# Solar_Water_Heater_Controller.net
KiCad netlist of a schematic drawn in Altium Designer
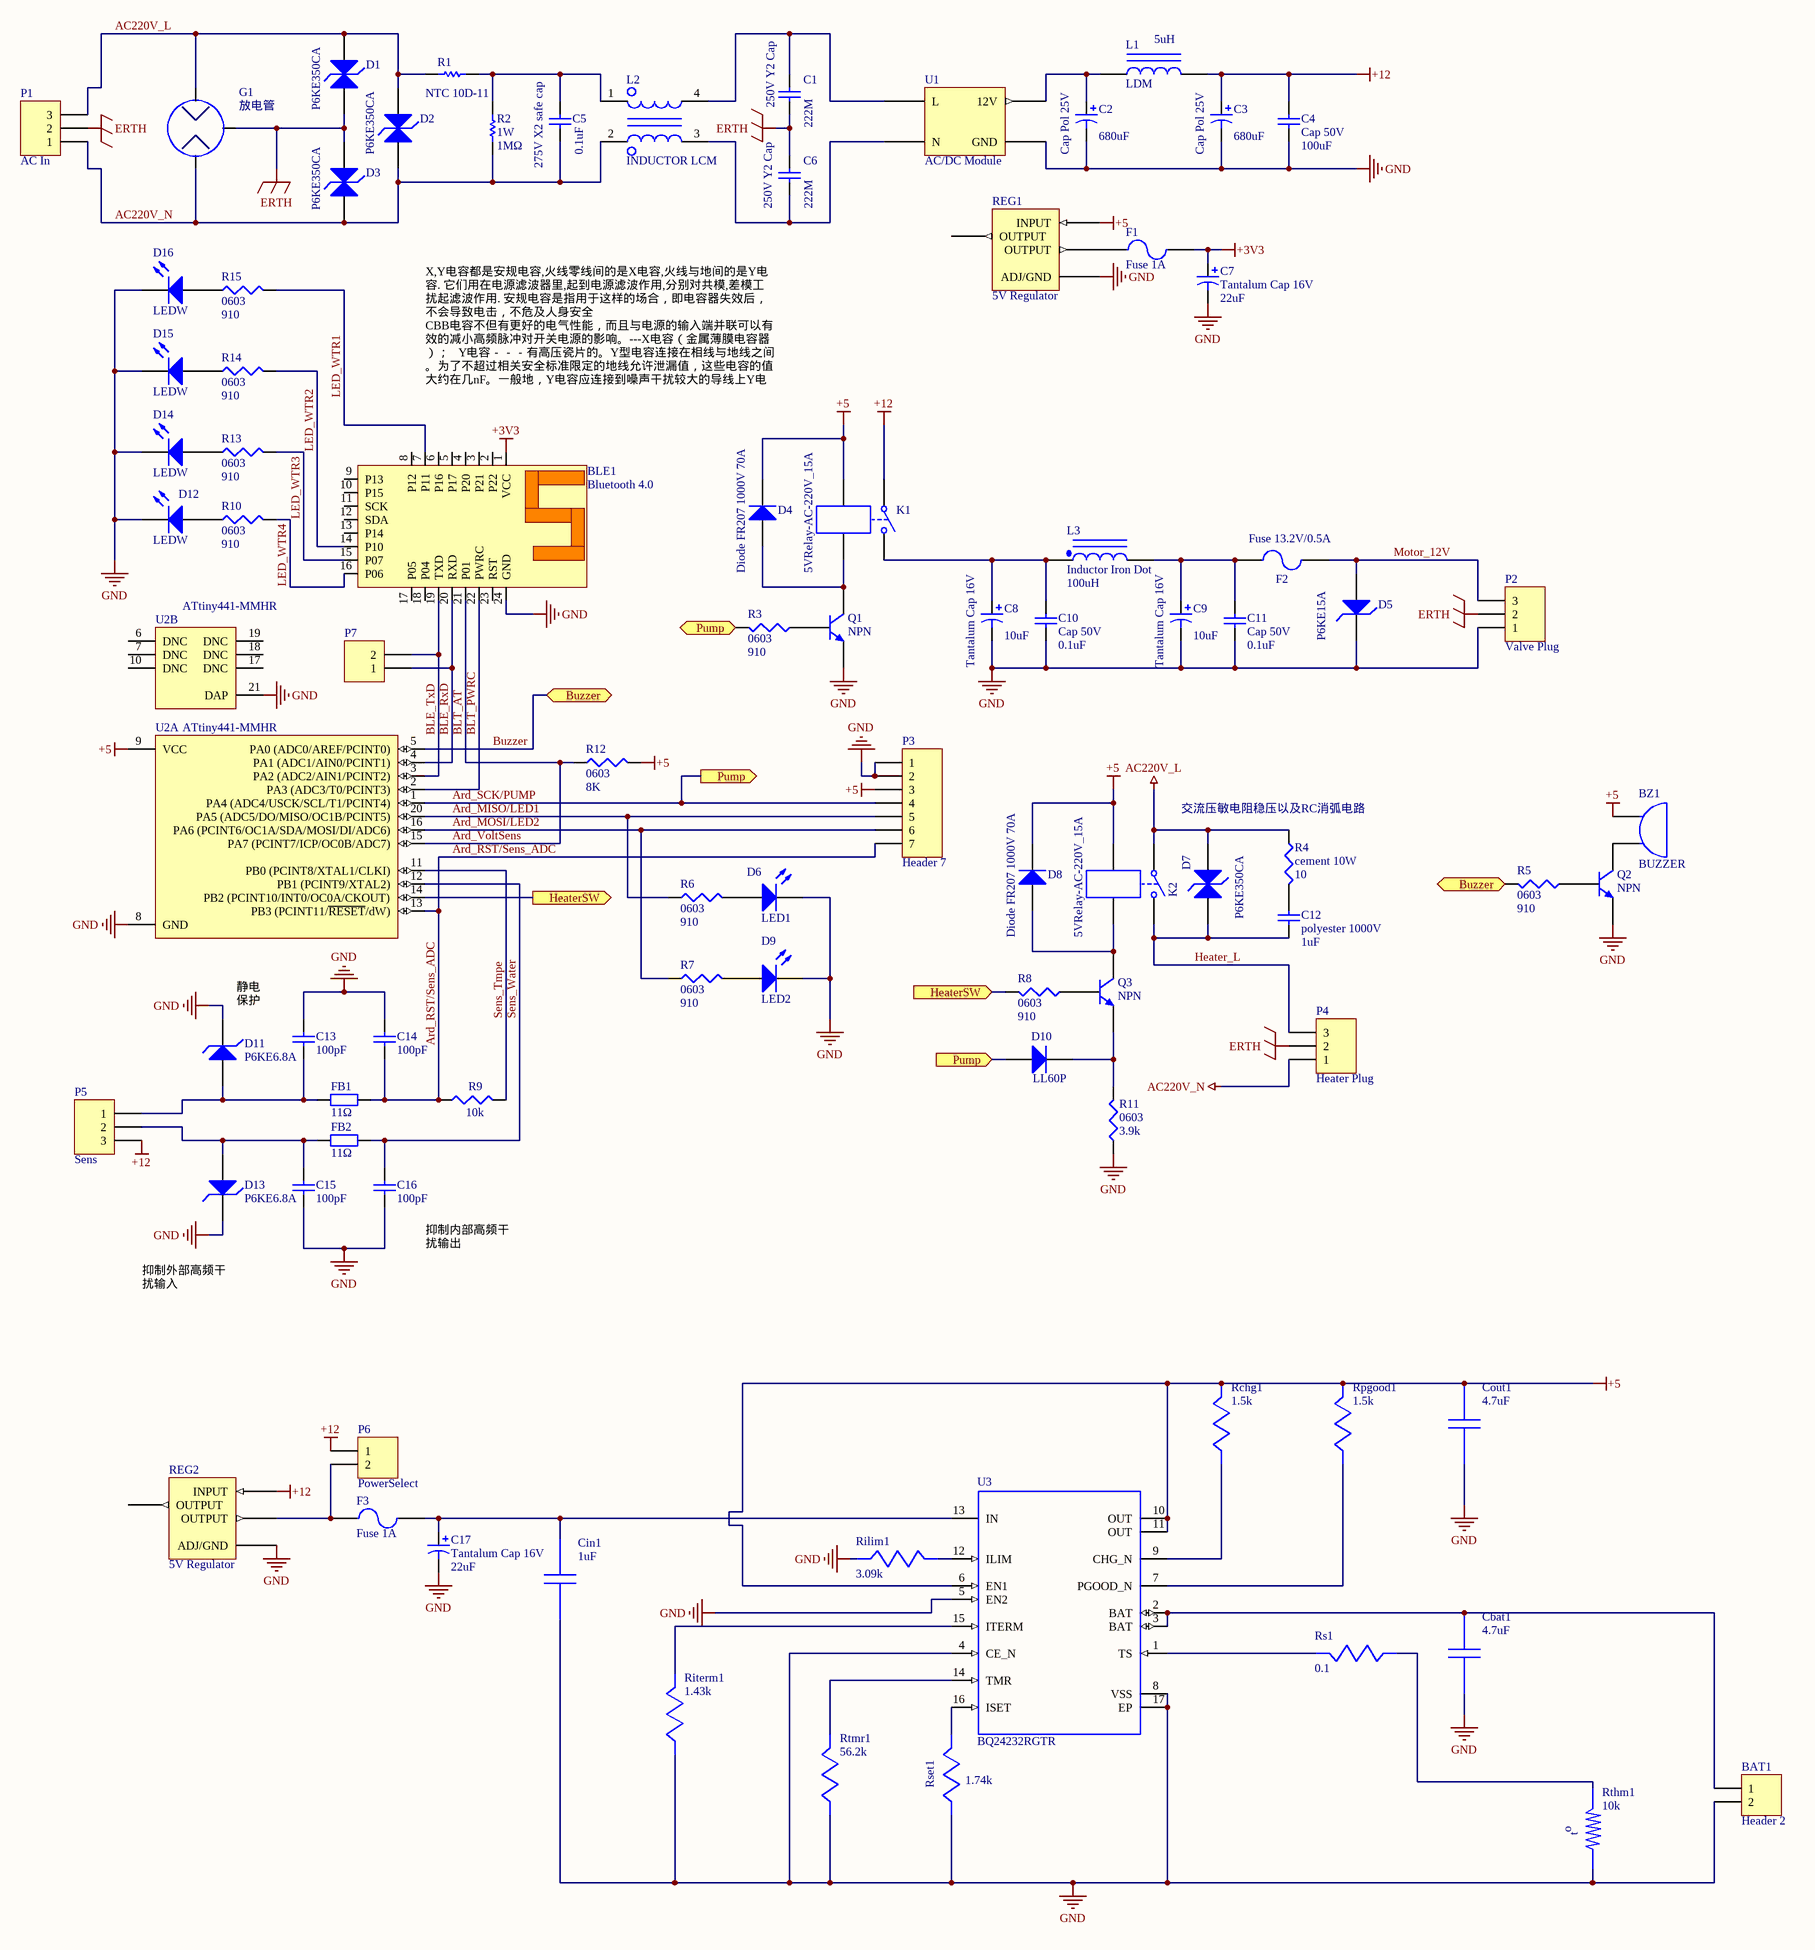
[diagram p0: Solar Water Heater Controller.SchDoc]

(export (version "E")
  (design (tool "Eeschema 10.0.6"))
  (components
    (comp (ref "BAT1")
      (value "Header 2")
      (footprint "HDR1X2")
      (description "Header, 2-Pin")
      (fields (field (name "PUBLISHER") "Altium Limited"))
      (libsource (lib "Miscellaneous Connectors") (part "Header 2"))
    )
    (comp (ref "BLE1")
      (value "Bluetooth 4.0")
      (footprint "JDY-08")
      (libsource (lib "JDY-08(原理图库)") (part "CC2541-Small"))
    )
    (comp (ref "BZ1")
      (value "BUZZER")
      (footprint "Buzzer")
      (description "5V有源蜂鸣器 电磁式 SOT塑封管 5V 12mm")
      (libsource (lib "杂元件库") (part "BUZZER"))
    )
    (comp (ref "C1")
      (value "250V Y2 Cap")
      (footprint "CapY2")
      (description "JNC222M 250V")
      (fields (field (name "ALTIUM_VALUE") "222M") (field (name "PUBLISHER") "Altium Limited"))
      (libsource (lib "Miscellaneous Devices") (part "Cap Semi"))
    )
    (comp (ref "C2")
      (value "Cap Pol 25V")
      (footprint "Cap680uf")
      (description "Polarized Capacitor (Radial)")
      (fields (field (name "ALTIUM_VALUE") "680uF") (field (name "PUBLISHER") "Altium Limited"))
      (libsource (lib "Miscellaneous Devices") (part "Cap Pol1"))
    )
    (comp (ref "C3")
      (value "Cap Pol 25V")
      (footprint "Cap680uf")
      (description "Polarized Capacitor (Radial)")
      (fields (field (name "ALTIUM_VALUE") "680uF") (field (name "PUBLISHER") "Altium Limited"))
      (libsource (lib "Miscellaneous Devices") (part "Cap Pol1"))
    )
    (comp (ref "C4")
      (value "Cap 50V")
      (footprint "1608[0603]")
      (description "Capacitor (Semiconductor SIM Model)")
      (fields (field (name "ALTIUM_VALUE") "100uF") (field (name "PUBLISHER") "Altium Limited"))
      (libsource (lib "Miscellaneous Devices") (part "Cap Semi"))
    )
    (comp (ref "C5")
      (value "275V X2 safe cap")
      (footprint "CapX2")
      (description "MPX104KV 275V X2安规电容")
      (fields (field (name "ALTIUM_VALUE") "0.1uF") (field (name "PUBLISHER") "Altium Limited"))
      (libsource (lib "Miscellaneous Devices") (part "Cap Semi"))
    )
    (comp (ref "C6")
      (value "250V Y2 Cap")
      (footprint "CapY2")
      (description "JNC222M 250V")
      (fields (field (name "ALTIUM_VALUE") "222M") (field (name "PUBLISHER") "Altium Limited"))
      (libsource (lib "Miscellaneous Devices") (part "Cap Semi"))
    )
    (comp (ref "C7")
      (value "Tantalum Cap 16V")
      (footprint "CAPC3216X175N")
      (description "22UF 16V 226K A3216 1206")
      (fields (field (name "ALTIUM_VALUE") "22uF") (field (name "PUBLISHER") "Altium Limited"))
      (libsource (lib "Miscellaneous Devices") (part "Cap Pol3"))
    )
    (comp (ref "C8")
      (value "Tantalum Cap 16V")
      (footprint "CAPC3216X175N")
      (fields (field (name "ALTIUM_VALUE") "10uF") (field (name "PUBLISHER") "Altium Limited"))
      (libsource (lib "Miscellaneous Devices") (part "Cap Pol3"))
    )
    (comp (ref "C9")
      (value "Tantalum Cap 16V")
      (footprint "CAPC3216X175N")
      (fields (field (name "ALTIUM_VALUE") "10uF") (field (name "PUBLISHER") "Altium Limited"))
      (libsource (lib "Miscellaneous Devices") (part "Cap Pol3"))
    )
    (comp (ref "C10")
      (value "Cap 50V")
      (footprint "1608[0603]")
      (description "Capacitor (Semiconductor SIM Model)")
      (fields (field (name "ALTIUM_VALUE") "0.1uF") (field (name "PUBLISHER") "Altium Limited"))
      (libsource (lib "Miscellaneous Devices") (part "Cap Semi"))
    )
    (comp (ref "C11")
      (value "Cap 50V")
      (footprint "1608[0603]")
      (description "Capacitor (Semiconductor SIM Model)")
      (fields (field (name "ALTIUM_VALUE") "0.1uF") (field (name "PUBLISHER") "Altium Limited"))
      (libsource (lib "Miscellaneous Devices") (part "Cap Semi"))
    )
    (comp (ref "C12")
      (value "polyester 1000V")
      (footprint "CBB21 Capacitor")
      (description "Capacitor (Semiconductor SIM Model)")
      (fields (field (name "ALTIUM_VALUE") "1uF") (field (name "PUBLISHER") "Altium Limited"))
      (libsource (lib "Miscellaneous Devices") (part "Cap Semi"))
    )
    (comp (ref "C13")
      (value "100pF")
      (footprint "1608[0603]")
      (description "Capacitor (Semiconductor SIM Model)")
      (fields (field (name "Comment") "Cap Semi") (field (name "PUBLISHER") "Altium Limited"))
      (libsource (lib "Miscellaneous Devices") (part "Cap 50V"))
    )
    (comp (ref "C14")
      (value "100pF")
      (footprint "1608[0603]")
      (description "Capacitor (Semiconductor SIM Model)")
      (fields (field (name "Comment") "Cap Semi") (field (name "PUBLISHER") "Altium Limited"))
      (libsource (lib "Miscellaneous Devices") (part "Cap 50V"))
    )
    (comp (ref "C15")
      (value "100pF")
      (footprint "1608[0603]")
      (description "Capacitor (Semiconductor SIM Model)")
      (fields (field (name "Comment") "Cap Semi") (field (name "PUBLISHER") "Altium Limited"))
      (libsource (lib "Miscellaneous Devices") (part "Cap 50V"))
    )
    (comp (ref "C16")
      (value "100pF")
      (footprint "1608[0603]")
      (description "Capacitor (Semiconductor SIM Model)")
      (fields (field (name "Comment") "Cap Semi") (field (name "PUBLISHER") "Altium Limited"))
      (libsource (lib "Miscellaneous Devices") (part "Cap 50V"))
    )
    (comp (ref "C17")
      (value "Tantalum Cap 16V")
      (footprint "CAPC3216X175N")
      (description "22UF 16V 226K A3216 1206")
      (fields (field (name "ALTIUM_VALUE") "22uF") (field (name "PUBLISHER") "Altium Limited"))
      (libsource (lib "Miscellaneous Devices") (part "Cap Pol3"))
    )
    (comp (ref "Cbat1")
      (value "4.7uF")
      (footprint "1608[0603]")
      (description "GRM219C81A475KE3")
      (fields (field (name "MANUFACTURER PART NUMBER") "GRM219C81A475KE34D"))
      (libsource (lib "TI WEBENCH") (part "Cbat"))
    )
    (comp (ref "Cin1")
      (value "1uF")
      (footprint "1608[0603]")
      (description "GRM188R61A105KA6")
      (fields (field (name "MANUFACTURER PART NUMBER") "GRM188R61A105KA61D"))
      (libsource (lib "TI WEBENCH") (part "Cin"))
    )
    (comp (ref "Cout1")
      (value "4.7uF")
      (footprint "1608[0603]")
      (description "GRM21BR61E475MA1")
      (fields (field (name "MANUFACTURER PART NUMBER") "GRM21BR61E475MA12L"))
      (libsource (lib "TI WEBENCH") (part "Cout"))
    )
    (comp (ref "D1")
      (value "P6KE350CA")
      (footprint "DO-15")
      (libsource (lib "HomeAutomation") (part "Diode TVS"))
    )
    (comp (ref "D2")
      (value "P6KE350CA")
      (footprint "DO-15")
      (libsource (lib "HomeAutomation") (part "Diode TVS"))
    )
    (comp (ref "D3")
      (value "P6KE350CA")
      (footprint "DO-15")
      (libsource (lib "HomeAutomation") (part "Diode TVS"))
    )
    (comp (ref "D4")
      (value "Diode FR207 1000V 70A")
      (footprint "DO-15")
      (description "High Conductance Fast Diode")
      (fields (field (name "PUBLISHER") "Altium Limited"))
      (libsource (lib "Miscellaneous Devices") (part "Diode 1N914"))
    )
    (comp (ref "D5")
      (value "P6KE15A")
      (footprint "DO-15")
      (libsource (lib "HomeAutomation") (part "Diode TVS_S"))
    )
    (comp (ref "D6")
      (value "LED1")
      (footprint "LED_1420")
      (description "Typical RED, GREEN, YELLOW, AMBER GaAs LED")
      (fields (field (name "PUBLISHER") "Altium Limited"))
      (libsource (lib "Miscellaneous Devices") (part "LED2"))
    )
    (comp (ref "D7")
      (value "P6KE350CA")
      (footprint "DO-15")
      (libsource (lib "HomeAutomation") (part "Diode TVS"))
    )
    (comp (ref "D8")
      (value "Diode FR207 1000V 70A")
      (footprint "DO-15")
      (description "High Conductance Fast Diode")
      (fields (field (name "PUBLISHER") "Altium Limited"))
      (libsource (lib "Miscellaneous Devices") (part "Diode 1N914"))
    )
    (comp (ref "D9")
      (value "LED2")
      (footprint "LED_1420")
      (description "Typical RED, GREEN, YELLOW, AMBER GaAs LED")
      (fields (field (name "PUBLISHER") "Altium Limited"))
      (libsource (lib "Miscellaneous Devices") (part "LED2"))
    )
    (comp (ref "D10")
      (value "LL60P")
      (footprint "LL60P")
      (fields (field (name "PUBLISHER") "Altium Limited"))
      (libsource (lib "Miscellaneous Devices") (part "Diode 1N914"))
    )
    (comp (ref "D11")
      (value "P6KE6.8A")
      (footprint "ONSC-SMB-2-403A-03_H_V")
      (libsource (lib "HomeAutomation") (part "Diode TVS_S"))
    )
    (comp (ref "D12")
      (value "LEDW")
      (footprint "LED_1420")
      (description "Typical RED, GREEN, YELLOW, AMBER GaAs LED")
      (fields (field (name "PUBLISHER") "Altium Limited"))
      (libsource (lib "Miscellaneous Devices") (part "LED2"))
    )
    (comp (ref "D13")
      (value "P6KE6.8A")
      (footprint "ONSC-SMB-2-403A-03_H_V")
      (description "P6KE6.8A SMB")
      (libsource (lib "HomeAutomation") (part "Diode TVS_S"))
    )
    (comp (ref "D14")
      (value "LEDW")
      (footprint "LED_1420")
      (description "Typical RED, GREEN, YELLOW, AMBER GaAs LED")
      (fields (field (name "PUBLISHER") "Altium Limited"))
      (libsource (lib "Miscellaneous Devices") (part "LED2"))
    )
    (comp (ref "D15")
      (value "LEDW")
      (footprint "LED_1420")
      (description "Typical RED, GREEN, YELLOW, AMBER GaAs LED")
      (fields (field (name "PUBLISHER") "Altium Limited"))
      (libsource (lib "Miscellaneous Devices") (part "LED2"))
    )
    (comp (ref "D16")
      (value "LEDW")
      (footprint "LED_1420")
      (description "Typical RED, GREEN, YELLOW, AMBER GaAs LED")
      (fields (field (name "PUBLISHER") "Altium Limited"))
      (libsource (lib "Miscellaneous Devices") (part "LED2"))
    )
    (comp (ref "F1")
      (value "Fuse 1A")
      (footprint "6-0805_L")
      (description "Fuse 1000mA 6V")
      (fields (field (name "PUBLISHER") "Altium Limited"))
      (libsource (lib "Miscellaneous Devices") (part "Fuse 2"))
    )
    (comp (ref "F2")
      (value "Fuse 13.2V/0.5A")
      (footprint "CAPC3216X100N")
      (description "1206SMD 500mA 13.2V/0.5A")
      (fields (field (name "PUBLISHER") "Altium Limited"))
      (libsource (lib "Miscellaneous Devices") (part "Fuse 2"))
    )
    (comp (ref "F3")
      (value "Fuse 1A")
      (footprint "6-0805_L")
      (description "Fuse 1000mA 6V")
      (fields (field (name "PUBLISHER") "Altium Limited"))
      (libsource (lib "Miscellaneous Devices") (part "Fuse 2"))
    )
    (comp (ref "FB1")
      (value "11Ω")
      (footprint "6-0805_L")
      (description "磁珠")
      (fields (field (name "Comment") "FB") (field (name "PUBLISHER") "Altium Limited"))
      (libsource (lib "Miscellaneous Devices") (part "Res2"))
    )
    (comp (ref "FB2")
      (value "11Ω")
      (footprint "6-0805_L")
      (description "磁珠")
      (fields (field (name "Comment") "FB") (field (name "PUBLISHER") "Altium Limited"))
      (libsource (lib "Miscellaneous Devices") (part "Res2"))
    )
    (comp (ref "G1")
      (value "放电管")
      (footprint "GAS TUBE")
      (description "3RM230L-8 230V")
      (libsource (lib "HomeAutomation") (part "GOT"))
    )
    (comp (ref "K1")
      (value "5VRelay-AC-220V_15A")
      (footprint "SZ-S105LM")
      (description "Single-Pole Single-Throw Relay SZ-S-105LM")
      (fields (field (name "PUBLISHER") "Altium Limited"))
      (libsource (lib "Miscellaneous Devices") (part "Relay-SPST"))
    )
    (comp (ref "K2")
      (value "5VRelay-AC-220V_15A")
      (footprint "SZ-S105LM")
      (description "Single-Pole Single-Throw Relay SZ-S-105LM")
      (fields (field (name "PUBLISHER") "Altium Limited"))
      (libsource (lib "Miscellaneous Devices") (part "Relay-SPST"))
    )
    (comp (ref "L1")
      (value "LDM")
      (footprint "CD54")
      (description "4R7H 贴片电感")
      (fields (field (name "ALTIUM_VALUE") "5uH"))
      (libsource (lib "杂元件库") (part "INDUCTOR IRON"))
    )
    (comp (ref "L2")
      (value "INDUCTOR LCM")
      (footprint "sumida CPFC1709/MS")
      (libsource (lib "杂元件库") (part "INDUCTOR LCM"))
    )
    (comp (ref "L3")
      (value "Inductor Iron Dot")
      (footprint "CD54")
      (description "贴片 CD54 100uH")
      (fields (field (name "ALTIUM_VALUE") "100uH") (field (name "PUBLISHER") "Altium Limited"))
      (libsource (lib "Miscellaneous Devices") (part "Inductor Iron Dot"))
    )
    (comp (ref "P1")
      (value "AC In")
      (footprint "3P 5.08mm Connecter")
      (description "Header, 3-Pin")
      (fields (field (name "PUBLISHER") "Altium Limited"))
      (libsource (lib "Miscellaneous Connectors") (part "Header 3"))
    )
    (comp (ref "P2")
      (value "Valve Plug")
      (footprint "3P 5.08mm Connecter")
      (description "Header, 3-Pin")
      (fields (field (name "PUBLISHER") "Altium Limited"))
      (libsource (lib "") (part "Header 3_1"))
    )
    (comp (ref "P3")
      (value "Header 7")
      (footprint "HDR1X7")
      (description "Header, 7-Pin")
      (fields (field (name "PUBLISHER") "Altium Limited"))
      (libsource (lib "Miscellaneous Connectors") (part "Header 7"))
    )
    (comp (ref "P4")
      (value "Heater Plug")
      (footprint "3P 5.08mm Connecter")
      (description "Header, 3-Pin")
      (fields (field (name "PUBLISHER") "Altium Limited"))
      (libsource (lib "") (part "Header 3_1"))
    )
    (comp (ref "P5")
      (value "Sens")
      (footprint "3P 5.08mm Connecter")
      (description "Header, 3-Pin")
      (fields (field (name "PUBLISHER") "Altium Limited"))
      (libsource (lib "") (part "Header 3_2"))
    )
    (comp (ref "P6")
      (value "PowerSelect")
      (footprint "J1-0603")
      (description "Header, 2-Pin")
      (fields (field (name "PUBLISHER") "Altium Limited"))
      (libsource (lib "Miscellaneous Connectors") (part "Header 2"))
    )
    (comp (ref "P7")
      (value "Serial")
      (footprint "HDR1X2")
      (description "Header, 2-Pin")
      (fields (field (name "PUBLISHER") "Altium Limited"))
      (libsource (lib "") (part "Header 2_1"))
    )
    (comp (ref "Q1")
      (value "NPN")
      (footprint "SOT23-3")
      (description "NPN Bipolar Transistor")
      (fields (field (name "PUBLISHER") "Altium Limited"))
      (libsource (lib "Miscellaneous Devices") (part "SS8550 NPN"))
    )
    (comp (ref "Q2")
      (value "NPN")
      (footprint "SOT23-3")
      (description "NPN Bipolar Transistor")
      (fields (field (name "PUBLISHER") "Altium Limited"))
      (libsource (lib "Miscellaneous Devices") (part "SS8550 NPN"))
    )
    (comp (ref "Q3")
      (value "NPN")
      (footprint "SOT23-3")
      (description "NPN Bipolar Transistor")
      (fields (field (name "PUBLISHER") "Altium Limited"))
      (libsource (lib "Miscellaneous Devices") (part "SS8550 NPN"))
    )
    (comp (ref "R1")
      (value "NTC 10D-11")
      (footprint "NTC 10D-11")
      (description "Semiconductor Resistor")
      (fields (field (name "PUBLISHER") "Altium Limited"))
      (libsource (lib "Miscellaneous Devices") (part "Res Semi"))
    )
    (comp (ref "R2")
      (value "1W")
      (footprint "AXIAL-0.5")
      (description "Semiconductor Resistor")
      (fields (field (name "ALTIUM_VALUE") "1MΩ") (field (name "PUBLISHER") "Altium Limited"))
      (libsource (lib "Miscellaneous Devices") (part "Res Semi"))
    )
    (comp (ref "R3")
      (value "0603")
      (footprint "J1-0603")
      (description "Resistor")
      (fields (field (name "ALTIUM_VALUE") "910") (field (name "PUBLISHER") "Altium Limited"))
      (libsource (lib "Miscellaneous Devices") (part "Res3"))
    )
    (comp (ref "R4")
      (value "cement 10W")
      (footprint "5W Resistor")
      (description "Resistor")
      (fields (field (name "ALTIUM_VALUE") "10") (field (name "PUBLISHER") "Altium Limited"))
      (libsource (lib "Miscellaneous Devices") (part "Res3"))
    )
    (comp (ref "R5")
      (value "0603")
      (footprint "J1-0603")
      (description "Resistor")
      (fields (field (name "ALTIUM_VALUE") "910") (field (name "PUBLISHER") "Altium Limited"))
      (libsource (lib "Miscellaneous Devices") (part "Res3"))
    )
    (comp (ref "R6")
      (value "0603")
      (footprint "J1-0603")
      (description "Resistor")
      (fields (field (name "ALTIUM_VALUE") "910") (field (name "PUBLISHER") "Altium Limited"))
      (libsource (lib "Miscellaneous Devices") (part "Res3"))
    )
    (comp (ref "R7")
      (value "0603")
      (footprint "J1-0603")
      (description "Resistor")
      (fields (field (name "ALTIUM_VALUE") "910") (field (name "PUBLISHER") "Altium Limited"))
      (libsource (lib "Miscellaneous Devices") (part "Res3"))
    )
    (comp (ref "R8")
      (value "0603")
      (footprint "J1-0603")
      (description "Resistor")
      (fields (field (name "ALTIUM_VALUE") "910") (field (name "PUBLISHER") "Altium Limited"))
      (libsource (lib "Miscellaneous Devices") (part "Res3"))
    )
    (comp (ref "R9")
      (value "10k")
      (footprint "J1-0603")
      (description "Resistor")
      (fields (field (name "Comment") "0603") (field (name "PUBLISHER") "Altium Limited"))
      (libsource (lib "Miscellaneous Devices") (part "Res3"))
    )
    (comp (ref "R10")
      (value "0603")
      (footprint "J1-0603")
      (description "Resistor")
      (fields (field (name "ALTIUM_VALUE") "910") (field (name "PUBLISHER") "Altium Limited"))
      (libsource (lib "Miscellaneous Devices") (part "Res3"))
    )
    (comp (ref "R11")
      (value "0603")
      (footprint "J1-0603")
      (description "Resistor")
      (fields (field (name "ALTIUM_VALUE") "3.9k") (field (name "PUBLISHER") "Altium Limited"))
      (libsource (lib "Miscellaneous Devices") (part "Res3"))
    )
    (comp (ref "R12")
      (value "0603")
      (footprint "J1-0603")
      (description "Resistor")
      (fields (field (name "ALTIUM_VALUE") "8K") (field (name "PUBLISHER") "Altium Limited"))
      (libsource (lib "Miscellaneous Devices") (part "Res3"))
    )
    (comp (ref "R13")
      (value "0603")
      (footprint "J1-0603")
      (description "Resistor")
      (fields (field (name "ALTIUM_VALUE") "910") (field (name "PUBLISHER") "Altium Limited"))
      (libsource (lib "Miscellaneous Devices") (part "Res3"))
    )
    (comp (ref "R14")
      (value "0603")
      (footprint "J1-0603")
      (description "Resistor")
      (fields (field (name "ALTIUM_VALUE") "910") (field (name "PUBLISHER") "Altium Limited"))
      (libsource (lib "Miscellaneous Devices") (part "Res3"))
    )
    (comp (ref "R15")
      (value "0603")
      (footprint "J1-0603")
      (description "Resistor")
      (fields (field (name "ALTIUM_VALUE") "910") (field (name "PUBLISHER") "Altium Limited"))
      (libsource (lib "Miscellaneous Devices") (part "Res3"))
    )
    (comp (ref "Rchg1")
      (value "1.5k")
      (footprint "J1-0603")
      (description "CRCW04021K50FKED")
      (libsource (lib "TI WEBENCH") (part "Rchg"))
    )
    (comp (ref "REG1")
      (value "5V Regulator")
      (footprint "SOT223")
      (libsource (lib "HomeAutomation") (part "AMS1117"))
    )
    (comp (ref "REG2")
      (value "5V Regulator")
      (footprint "SOT223")
      (libsource (lib "HomeAutomation") (part "AMS1117"))
    )
    (comp (ref "Rilim1")
      (value "3.09k")
      (footprint "J1-0603")
      (description "CRCW04023K09FKED")
      (libsource (lib "TI WEBENCH") (part "Rilim"))
    )
    (comp (ref "Riterm1")
      (value "1.43k")
      (footprint "J1-0603")
      (description "CRCW04021K43FKED")
      (libsource (lib "TI WEBENCH") (part "Riterm"))
    )
    (comp (ref "Rpgood1")
      (value "1.5k")
      (footprint "J1-0603")
      (description "CRCW04021K50FKED")
      (libsource (lib "TI WEBENCH") (part "Rpgood"))
    )
    (comp (ref "Rs1")
      (value "0.1")
      (footprint "J1-0603")
      (description "ERJ-2BSFR10X")
      (libsource (lib "TI WEBENCH") (part "Rs"))
    )
    (comp (ref "Rset1")
      (value "1.74k")
      (footprint "J1-0603")
      (description "CRCW04021K74FKED")
      (libsource (lib "TI WEBENCH") (part "Rset"))
    )
    (comp (ref "Rthm1")
      (value "10k")
      (footprint "J1-0603")
      (description "NCP15XH103E03RC")
      (libsource (lib "TI WEBENCH") (part "Rthm"))
    )
    (comp (ref "Rtmr1")
      (value "56.2k")
      (footprint "J1-0603")
      (description "CRCW040256K2FKED")
      (libsource (lib "TI WEBENCH") (part "Rtmr"))
    )
    (comp (ref "U1")
      (value "AC/DC Module")
      (footprint "HB12N10-2836")
      (description "AC/DC Module 220V AC / 12V DC 1A")
      (libsource (lib "HomeAutomation") (part "AC/DC Moule"))
    )
    (comp (ref "U2")
      (value "ATtiny441-MMHR")
      (footprint "20M2_N")
      (libsource (lib "Atmel Microcontroller tinyAVR") (part "ATtiny44A-MMHR"))
    )
    (comp (ref "U3")
      (value "BQ24232RGTR")
      (footprint "RGT16-1700X1700TP")
      (fields (field (name "PACKAGEREFERENCE") "BQ24232RGTR"))
      (libsource (lib "TI WEBENCH") (part "U1"))
    )
  )
  (nets
    (net (code "1") (name "+3V3") (class "Default")
      (node (ref "BLE1") (pin "1") (pinfunction "VCC_1") (pintype "passive"))
      (node (ref "C7") (pin "1") (pinfunction "1_1") (pintype "passive"))
      (node (ref "F1") (pin "2") (pinfunction "2_2") (pintype "passive"))
    )
    (net (code "2") (name "+5") (class "Default")
      (node (ref "BZ1") (pin "1") (pinfunction "A_1") (pintype "passive"))
      (node (ref "Cout1") (pin "1") (pinfunction "1_1") (pintype "passive"))
      (node (ref "D4") (pin "2") (pinfunction "K_2") (pintype "passive"))
      (node (ref "D8") (pin "2") (pinfunction "K_2") (pintype "passive"))
      (node (ref "K1") (pin "3") (pinfunction "3_3") (pintype "passive"))
      (node (ref "K2") (pin "3") (pinfunction "3_3") (pintype "passive"))
      (node (ref "P3") (pin "3") (pinfunction "3_3") (pintype "passive"))
      (node (ref "R12") (pin "2") (pinfunction "2_2") (pintype "passive"))
      (node (ref "REG1") (pin "3") (pinfunction "INPUT_3") (pintype "input"))
      (node (ref "Rchg1") (pin "1") (pinfunction "1_1") (pintype "passive"))
      (node (ref "Rpgood1") (pin "1") (pinfunction "1_1") (pintype "passive"))
      (node (ref "U2") (pin "9") (pinfunction "VCC_9") (pintype "power_in"))
      (node (ref "U3") (pin "10") (pinfunction "OUT_10") (pintype "power_in"))
      (node (ref "U3") (pin "11") (pinfunction "OUT_11") (pintype "power_in"))
      (node (ref "U3") (pin "6") (pinfunction "EN1_6") (pintype "input"))
    )
    (net (code "3") (name "+12") (class "Default")
      (node (ref "C3") (pin "1") (pinfunction "1_1") (pintype "passive"))
      (node (ref "C4") (pin "2") (pinfunction "2_2") (pintype "passive"))
      (node (ref "K1") (pin "1") (pinfunction "1_1") (pintype "passive"))
      (node (ref "L1") (pin "2") (pinfunction "2_2") (pintype "passive"))
      (node (ref "P5") (pin "3") (pinfunction "3_3") (pintype "passive"))
      (node (ref "P6") (pin "1") (pinfunction "1_1") (pintype "passive"))
      (node (ref "REG2") (pin "3") (pinfunction "INPUT_3") (pintype "input"))
    )
    (net (code "4") (name "/Ard_MISO{slash}LED1") (class "Default")
      (node (ref "P3") (pin "5") (pinfunction "5_5") (pintype "passive"))
      (node (ref "R6") (pin "1") (pinfunction "1_1") (pintype "passive"))
      (node (ref "U2") (pin "20") (pinfunction "PA5_(ADC5/DO/MISO/OC1B/PCINT5)_20") (pintype "bidirectional"))
    )
    (net (code "5") (name "/Ard_MOSI{slash}LED2") (class "Default")
      (node (ref "P3") (pin "6") (pinfunction "6_6") (pintype "passive"))
      (node (ref "R7") (pin "1") (pinfunction "1_1") (pintype "passive"))
      (node (ref "U2") (pin "16") (pinfunction "PA6_(PCINT6/OC1A/SDA/MOSI/DI/ADC6)_16") (pintype "bidirectional"))
    )
    (net (code "6") (name "/Ard_RST{slash}Sens_ADC") (class "Default")
      (node (ref "C14") (pin "1") (pinfunction "1_1") (pintype "passive"))
      (node (ref "FB1") (pin "2") (pinfunction "2_2") (pintype "passive"))
      (node (ref "P3") (pin "7") (pinfunction "7_7") (pintype "passive"))
      (node (ref "R9") (pin "2") (pinfunction "2_2") (pintype "passive"))
      (node (ref "U2") (pin "13") (pinfunction "PB3_(PCINT11/~{RESET}/dW)_13") (pintype "bidirectional"))
    )
    (net (code "7") (name "/Ard_SCK{slash}PUMP") (class "Default")
      (node (ref "D10") (pin "1") (pinfunction "A_1") (pintype "passive"))
      (node (ref "P3") (pin "4") (pinfunction "4_4") (pintype "passive"))
      (node (ref "R3") (pin "2") (pinfunction "2_2") (pintype "passive"))
      (node (ref "U2") (pin "1") (pinfunction "PA4_(ADC4/USCK/SCL/T1/PCINT4)_1") (pintype "bidirectional"))
    )
    (net (code "8") (name "/Ard_VoltSens") (class "Default")
      (node (ref "BLE1") (pin "21") (pinfunction "P01_21") (pintype "passive"))
      (node (ref "R12") (pin "1") (pinfunction "1_1") (pintype "passive"))
      (node (ref "U2") (pin "15") (pinfunction "PA7_(PCINT7/ICP/OC0B/ADC7)_15") (pintype "bidirectional"))
    )
    (net (code "9") (name "/BLE_RxD") (class "Default")
      (node (ref "BLE1") (pin "20") (pinfunction "RXD_20") (pintype "passive"))
      (node (ref "P7") (pin "1") (pinfunction "1_1") (pintype "passive"))
      (node (ref "U2") (pin "4") (pinfunction "PA1_(ADC1/AIN0/PCINT1)_4") (pintype "bidirectional"))
    )
    (net (code "10") (name "/BLE_TxD") (class "Default")
      (node (ref "BLE1") (pin "19") (pinfunction "TXD_19") (pintype "passive"))
      (node (ref "P7") (pin "2") (pinfunction "2_2") (pintype "passive"))
      (node (ref "U2") (pin "3") (pinfunction "PA2_(ADC2/AIN1/PCINT2)_3") (pintype "bidirectional"))
    )
    (net (code "11") (name "/BLT_PWRC") (class "Default")
      (node (ref "BLE1") (pin "22") (pinfunction "PWRC_22") (pintype "passive"))
      (node (ref "U2") (pin "2") (pinfunction "PA3_(ADC3/T0/PCINT3)_2") (pintype "bidirectional"))
    )
    (net (code "12") (name "/Buzzer") (class "Default")
      (node (ref "R5") (pin "2") (pinfunction "2_2") (pintype "passive"))
      (node (ref "U2") (pin "5") (pinfunction "PA0_(ADC0/AREF/PCINT0)_5") (pintype "bidirectional"))
    )
    (net (code "13") (name "/HeaterSW") (class "Default")
      (node (ref "R8") (pin "2") (pinfunction "2_2") (pintype "passive"))
      (node (ref "U2") (pin "14") (pinfunction "PB2_(PCINT10/INT0/OC0A/CKOUT)_14") (pintype "bidirectional"))
    )
    (net (code "14") (name "/Heater_L") (class "Default")
      (node (ref "C12") (pin "2") (pinfunction "2_2") (pintype "passive"))
      (node (ref "D7") (pin "1") (pinfunction "A_1") (pintype "passive"))
      (node (ref "K2") (pin "2") (pinfunction "2_2") (pintype "passive"))
      (node (ref "P4") (pin "3") (pinfunction "3_3") (pintype "passive"))
    )
    (net (code "15") (name "/LED_WTR1") (class "Default")
      (node (ref "BLE1") (pin "7") (pinfunction "P11_7") (pintype "passive"))
      (node (ref "R15") (pin "1") (pinfunction "1_1") (pintype "passive"))
    )
    (net (code "16") (name "/LED_WTR2") (class "Default")
      (node (ref "BLE1") (pin "14") (pinfunction "P10_14") (pintype "passive"))
      (node (ref "R14") (pin "1") (pinfunction "1_1") (pintype "passive"))
    )
    (net (code "17") (name "/LED_WTR3") (class "Default")
      (node (ref "BLE1") (pin "15") (pinfunction "P07_15") (pintype "passive"))
      (node (ref "R13") (pin "1") (pinfunction "1_1") (pintype "passive"))
    )
    (net (code "18") (name "/LED_WTR4") (class "Default")
      (node (ref "BLE1") (pin "16") (pinfunction "P06_16") (pintype "passive"))
      (node (ref "R10") (pin "1") (pinfunction "1_1") (pintype "passive"))
    )
    (net (code "19") (name "/Motor_12V") (class "Default")
      (node (ref "D5") (pin "1") (pinfunction "A_1") (pintype "passive"))
      (node (ref "F2") (pin "1") (pinfunction "1_1") (pintype "passive"))
      (node (ref "P2") (pin "3") (pinfunction "3_3") (pintype "passive"))
    )
    (net (code "20") (name "/Sens_Tmpe") (class "Default")
      (node (ref "R9") (pin "1") (pinfunction "1_1") (pintype "passive"))
      (node (ref "U2") (pin "11") (pinfunction "PB0_(PCINT8/XTAL1/CLKI)_11") (pintype "bidirectional"))
    )
    (net (code "21") (name "/Sens_Water") (class "Default")
      (node (ref "C16") (pin "1") (pinfunction "1_1") (pintype "passive"))
      (node (ref "FB2") (pin "2") (pinfunction "2_2") (pintype "passive"))
      (node (ref "U2") (pin "12") (pinfunction "PB1_(PCINT9/XTAL2)_12") (pintype "bidirectional"))
    )
    (net (code "22") (name "AC220V_L") (class "Default")
      (node (ref "D1") (pin "2") (pinfunction "K_2") (pintype "passive"))
      (node (ref "D2") (pin "2") (pinfunction "K_2") (pintype "passive"))
      (node (ref "D7") (pin "2") (pinfunction "K_2") (pintype "passive"))
      (node (ref "G1") (pin "1") (pinfunction "1_1") (pintype "passive"))
      (node (ref "K2") (pin "1") (pinfunction "1_1") (pintype "passive"))
      (node (ref "P1") (pin "3") (pinfunction "3_3") (pintype "passive"))
      (node (ref "R1") (pin "2") (pinfunction "2_2") (pintype "passive"))
      (node (ref "R4") (pin "1") (pinfunction "1_1") (pintype "passive"))
    )
    (net (code "23") (name "AC220V_N") (class "Default")
      (node (ref "C5") (pin "2") (pinfunction "2_2") (pintype "passive"))
      (node (ref "D2") (pin "1") (pinfunction "A_1") (pintype "passive"))
      (node (ref "D3") (pin "1") (pinfunction "A_1") (pintype "passive"))
      (node (ref "G1") (pin "3") (pinfunction "3_3") (pintype "passive"))
      (node (ref "L2") (pin "2") (pinfunction "2_2") (pintype "passive"))
      (node (ref "P1") (pin "1") (pinfunction "1_1") (pintype "passive"))
      (node (ref "P4") (pin "1") (pinfunction "1_1") (pintype "passive"))
      (node (ref "R2") (pin "1") (pinfunction "1_1") (pintype "passive"))
    )
    (net (code "24") (name "ERTH") (class "Default")
      (node (ref "C1") (pin "1") (pinfunction "1_1") (pintype "passive"))
      (node (ref "C6") (pin "2") (pinfunction "2_2") (pintype "passive"))
      (node (ref "D1") (pin "1") (pinfunction "A_1") (pintype "passive"))
      (node (ref "D3") (pin "2") (pinfunction "K_2") (pintype "passive"))
      (node (ref "G1") (pin "2") (pinfunction "7_2") (pintype "passive"))
      (node (ref "P1") (pin "2") (pinfunction "2_2") (pintype "passive"))
      (node (ref "P2") (pin "2") (pinfunction "2_2") (pintype "passive"))
      (node (ref "P4") (pin "2") (pinfunction "2_2") (pintype "passive"))
    )
    (net (code "25") (name "GND") (class "Default")
      (node (ref "BAT1") (pin "2") (pinfunction "2_2") (pintype "passive"))
      (node (ref "BLE1") (pin "24") (pinfunction "GND_24") (pintype "passive"))
      (node (ref "C10") (pin "1") (pinfunction "1_1") (pintype "passive"))
      (node (ref "C11") (pin "1") (pinfunction "1_1") (pintype "passive"))
      (node (ref "C13") (pin "2") (pinfunction "2_2") (pintype "passive"))
      (node (ref "C14") (pin "2") (pinfunction "2_2") (pintype "passive"))
      (node (ref "C15") (pin "2") (pinfunction "2_2") (pintype "passive"))
      (node (ref "C16") (pin "2") (pinfunction "2_2") (pintype "passive"))
      (node (ref "C17") (pin "2") (pinfunction "2_2") (pintype "passive"))
      (node (ref "C2") (pin "2") (pinfunction "2_2") (pintype "passive"))
      (node (ref "C3") (pin "2") (pinfunction "2_2") (pintype "passive"))
      (node (ref "C4") (pin "1") (pinfunction "1_1") (pintype "passive"))
      (node (ref "C7") (pin "2") (pinfunction "2_2") (pintype "passive"))
      (node (ref "C8") (pin "2") (pinfunction "2_2") (pintype "passive"))
      (node (ref "C9") (pin "2") (pinfunction "2_2") (pintype "passive"))
      (node (ref "Cbat1") (pin "2") (pinfunction "2_2") (pintype "passive"))
      (node (ref "Cin1") (pin "2") (pinfunction "2_2") (pintype "passive"))
      (node (ref "Cout1") (pin "2") (pinfunction "2_2") (pintype "passive"))
      (node (ref "D11") (pin "2") (pinfunction "K_2") (pintype "passive"))
      (node (ref "D12") (pin "2") (pinfunction "K_2") (pintype "passive"))
      (node (ref "D13") (pin "2") (pinfunction "K_2") (pintype "passive"))
      (node (ref "D14") (pin "2") (pinfunction "K_2") (pintype "passive"))
      (node (ref "D15") (pin "2") (pinfunction "K_2") (pintype "passive"))
      (node (ref "D16") (pin "2") (pinfunction "K_2") (pintype "passive"))
      (node (ref "D5") (pin "2") (pinfunction "K_2") (pintype "passive"))
      (node (ref "D6") (pin "2") (pinfunction "K_2") (pintype "passive"))
      (node (ref "D9") (pin "2") (pinfunction "K_2") (pintype "passive"))
      (node (ref "P2") (pin "1") (pinfunction "1_1") (pintype "passive"))
      (node (ref "P3") (pin "1") (pinfunction "1_1") (pintype "passive"))
      (node (ref "P3") (pin "2") (pinfunction "2_2") (pintype "passive"))
      (node (ref "Q1") (pin "3") (pinfunction "E_3") (pintype "passive"))
      (node (ref "Q2") (pin "3") (pinfunction "E_3") (pintype "passive"))
      (node (ref "R11") (pin "1") (pinfunction "1_1") (pintype "passive"))
      (node (ref "REG1") (pin "1") (pinfunction "ADJ/GND_1") (pintype "passive"))
      (node (ref "REG2") (pin "1") (pinfunction "ADJ/GND_1") (pintype "passive"))
      (node (ref "Rilim1") (pin "2") (pinfunction "2_2") (pintype "passive"))
      (node (ref "Riterm1") (pin "2") (pinfunction "2_2") (pintype "passive"))
      (node (ref "Rset1") (pin "2") (pinfunction "2_2") (pintype "passive"))
      (node (ref "Rthm1") (pin "1") (pinfunction "1_1") (pintype "passive"))
      (node (ref "Rtmr1") (pin "2") (pinfunction "2_2") (pintype "passive"))
      (node (ref "U1") (pin "5") (pinfunction "GND_5") (pintype "passive"))
      (node (ref "U2") (pin "21") (pinfunction "DAP_21") (pintype "power_in"))
      (node (ref "U2") (pin "8") (pinfunction "GND_8") (pintype "power_in"))
      (node (ref "U3") (pin "17") (pinfunction "EP_17") (pintype "power_in"))
      (node (ref "U3") (pin "4") (pinfunction "CE_N_4") (pintype "input"))
      (node (ref "U3") (pin "5") (pinfunction "EN2_5") (pintype "input"))
      (node (ref "U3") (pin "8") (pinfunction "VSS_8") (pintype "power_in"))
    )
    (net (code "26") (name "Net-(BAT1-Pad1)") (class "Default")
      (node (ref "BAT1") (pin "1") (pinfunction "1_1") (pintype "passive"))
      (node (ref "Cbat1") (pin "1") (pinfunction "1_1") (pintype "passive"))
      (node (ref "U3") (pin "2") (pinfunction "BAT_2") (pintype "bidirectional"))
      (node (ref "U3") (pin "3") (pinfunction "BAT_3") (pintype "bidirectional"))
    )
    (net (code "27") (name "Net-(BZ1-B)") (class "Default")
      (node (ref "BZ1") (pin "2") (pinfunction "B_2") (pintype "passive"))
      (node (ref "Q2") (pin "1") (pinfunction "C_1") (pintype "passive"))
    )
    (net (code "28") (name "Net-(C5-Pad1)") (class "Default")
      (node (ref "C5") (pin "1") (pinfunction "1_1") (pintype "passive"))
      (node (ref "L2") (pin "1") (pinfunction "1_1") (pintype "passive"))
      (node (ref "R1") (pin "1") (pinfunction "1_1") (pintype "passive"))
      (node (ref "R2") (pin "2") (pinfunction "2_2") (pintype "passive"))
    )
    (net (code "29") (name "Net-(C10-Pad2)") (class "Default")
      (node (ref "C10") (pin "2") (pinfunction "2_2") (pintype "passive"))
      (node (ref "C8") (pin "1") (pinfunction "1_1") (pintype "passive"))
      (node (ref "K1") (pin "2") (pinfunction "2_2") (pintype "passive"))
      (node (ref "L3") (pin "1") (pinfunction "1_1") (pintype "passive"))
    )
    (net (code "30") (name "Net-(C11-Pad2)") (class "Default")
      (node (ref "C11") (pin "2") (pinfunction "2_2") (pintype "passive"))
      (node (ref "C9") (pin "1") (pinfunction "1_1") (pintype "passive"))
      (node (ref "F2") (pin "2") (pinfunction "2_2") (pintype "passive"))
      (node (ref "L3") (pin "2") (pinfunction "2_2") (pintype "passive"))
    )
    (net (code "31") (name "Net-(C12-Pad1)") (class "Default")
      (node (ref "C12") (pin "1") (pinfunction "1_1") (pintype "passive"))
      (node (ref "R4") (pin "2") (pinfunction "2_2") (pintype "passive"))
    )
    (net (code "32") (name "Net-(D4-A)") (class "Default")
      (node (ref "D4") (pin "1") (pinfunction "A_1") (pintype "passive"))
      (node (ref "K1") (pin "4") (pinfunction "4_4") (pintype "passive"))
      (node (ref "Q1") (pin "1") (pinfunction "C_1") (pintype "passive"))
    )
    (net (code "33") (name "Net-(D6-A)") (class "Default")
      (node (ref "D6") (pin "1") (pinfunction "A_1") (pintype "passive"))
      (node (ref "R6") (pin "2") (pinfunction "2_2") (pintype "passive"))
    )
    (net (code "34") (name "Net-(D8-A)") (class "Default")
      (node (ref "D8") (pin "1") (pinfunction "A_1") (pintype "passive"))
      (node (ref "K2") (pin "4") (pinfunction "4_4") (pintype "passive"))
      (node (ref "Q3") (pin "1") (pinfunction "C_1") (pintype "passive"))
    )
    (net (code "35") (name "Net-(D9-A)") (class "Default")
      (node (ref "D9") (pin "1") (pinfunction "A_1") (pintype "passive"))
      (node (ref "R7") (pin "2") (pinfunction "2_2") (pintype "passive"))
    )
    (net (code "36") (name "Net-(D10-K)") (class "Default")
      (node (ref "D10") (pin "2") (pinfunction "K_2") (pintype "passive"))
      (node (ref "Q3") (pin "3") (pinfunction "E_3") (pintype "passive"))
      (node (ref "R11") (pin "2") (pinfunction "2_2") (pintype "passive"))
    )
    (net (code "37") (name "Net-(D11-A)") (class "Default")
      (node (ref "C13") (pin "1") (pinfunction "1_1") (pintype "passive"))
      (node (ref "D11") (pin "1") (pinfunction "A_1") (pintype "passive"))
      (node (ref "FB1") (pin "1") (pinfunction "1_1") (pintype "passive"))
      (node (ref "P5") (pin "1") (pinfunction "1_1") (pintype "passive"))
    )
    (net (code "38") (name "Net-(D12-A)") (class "Default")
      (node (ref "D12") (pin "1") (pinfunction "A_1") (pintype "passive"))
      (node (ref "R10") (pin "2") (pinfunction "2_2") (pintype "passive"))
    )
    (net (code "39") (name "Net-(D13-A)") (class "Default")
      (node (ref "C15") (pin "1") (pinfunction "1_1") (pintype "passive"))
      (node (ref "D13") (pin "1") (pinfunction "A_1") (pintype "passive"))
      (node (ref "FB2") (pin "1") (pinfunction "1_1") (pintype "passive"))
      (node (ref "P5") (pin "2") (pinfunction "2_2") (pintype "passive"))
    )
    (net (code "40") (name "Net-(D14-A)") (class "Default")
      (node (ref "D14") (pin "1") (pinfunction "A_1") (pintype "passive"))
      (node (ref "R13") (pin "2") (pinfunction "2_2") (pintype "passive"))
    )
    (net (code "41") (name "Net-(D15-A)") (class "Default")
      (node (ref "D15") (pin "1") (pinfunction "A_1") (pintype "passive"))
      (node (ref "R14") (pin "2") (pinfunction "2_2") (pintype "passive"))
    )
    (net (code "42") (name "Net-(D16-A)") (class "Default")
      (node (ref "D16") (pin "1") (pinfunction "A_1") (pintype "passive"))
      (node (ref "R15") (pin "2") (pinfunction "2_2") (pintype "passive"))
    )
    (net (code "43") (name "Net-(F1-Pad1)") (class "Default")
      (node (ref "F1") (pin "1") (pinfunction "1_1") (pintype "passive"))
      (node (ref "REG1") (pin "2") (pinfunction "OUTPUT_2") (pintype "output"))
    )
    (net (code "44") (name "Net-(F3-Pad1)") (class "Default")
      (node (ref "F3") (pin "1") (pinfunction "1_1") (pintype "passive"))
      (node (ref "P6") (pin "2") (pinfunction "2_2") (pintype "passive"))
      (node (ref "REG2") (pin "2") (pinfunction "OUTPUT_2") (pintype "output"))
    )
    (net (code "45") (name "Net-(Q1-B)") (class "Default")
      (node (ref "Q1") (pin "2") (pinfunction "B_2") (pintype "passive"))
      (node (ref "R3") (pin "1") (pinfunction "1_1") (pintype "passive"))
    )
    (net (code "46") (name "Net-(Q2-B)") (class "Default")
      (node (ref "Q2") (pin "2") (pinfunction "B_2") (pintype "passive"))
      (node (ref "R5") (pin "1") (pinfunction "1_1") (pintype "passive"))
    )
    (net (code "47") (name "Net-(Q3-B)") (class "Default")
      (node (ref "Q3") (pin "2") (pinfunction "B_2") (pintype "passive"))
      (node (ref "R8") (pin "1") (pinfunction "1_1") (pintype "passive"))
    )
    (net (code "48") (name "Net-(Rs1-Pad2)") (class "Default")
      (node (ref "Rs1") (pin "2") (pinfunction "2_2") (pintype "passive"))
      (node (ref "Rthm1") (pin "2") (pinfunction "2_2") (pintype "passive"))
    )
    (net (code "49") (name "Net-(U1-12V)") (class "Default")
      (node (ref "C2") (pin "1") (pinfunction "1_1") (pintype "passive"))
      (node (ref "L1") (pin "1") (pinfunction "1_1") (pintype "passive"))
      (node (ref "U1") (pin "3") (pinfunction "12V_3") (pintype "output"))
    )
    (net (code "50") (name "Net-(U1-L)") (class "Default")
      (node (ref "C1") (pin "2") (pinfunction "2_2") (pintype "passive"))
      (node (ref "L2") (pin "4") (pinfunction "4_4") (pintype "passive"))
      (node (ref "U1") (pin "1") (pinfunction "L_1") (pintype "power_in"))
    )
    (net (code "51") (name "Net-(U1-N)") (class "Default")
      (node (ref "C6") (pin "1") (pinfunction "1_1") (pintype "passive"))
      (node (ref "L2") (pin "3") (pinfunction "4_3") (pintype "passive"))
      (node (ref "U1") (pin "2") (pinfunction "N_2") (pintype "power_in"))
    )
    (net (code "52") (name "Net-(U3-CHG_N)") (class "Default")
      (node (ref "Rchg1") (pin "2") (pinfunction "2_2") (pintype "passive"))
      (node (ref "U3") (pin "9") (pinfunction "CHG_N_9") (pintype "open_collector"))
    )
    (net (code "53") (name "Net-(U3-ILIM)") (class "Default")
      (node (ref "Rilim1") (pin "1") (pinfunction "1_1") (pintype "passive"))
      (node (ref "U3") (pin "12") (pinfunction "ILIM_12") (pintype "input"))
    )
    (net (code "54") (name "Net-(U3-IN)") (class "Default")
      (node (ref "C17") (pin "1") (pinfunction "1_1") (pintype "passive"))
      (node (ref "Cin1") (pin "1") (pinfunction "1_1") (pintype "passive"))
      (node (ref "F3") (pin "2") (pinfunction "2_2") (pintype "passive"))
      (node (ref "U3") (pin "13") (pinfunction "IN_13") (pintype "power_in"))
    )
    (net (code "55") (name "Net-(U3-ISET)") (class "Default")
      (node (ref "Rset1") (pin "1") (pinfunction "1_1") (pintype "passive"))
      (node (ref "U3") (pin "16") (pinfunction "ISET_16") (pintype "input"))
    )
    (net (code "56") (name "Net-(U3-ITERM)") (class "Default")
      (node (ref "Riterm1") (pin "1") (pinfunction "1_1") (pintype "passive"))
      (node (ref "U3") (pin "15") (pinfunction "ITERM_15") (pintype "input"))
    )
    (net (code "57") (name "Net-(U3-PGOOD_N)") (class "Default")
      (node (ref "Rpgood1") (pin "2") (pinfunction "2_2") (pintype "passive"))
      (node (ref "U3") (pin "7") (pinfunction "PGOOD_N_7") (pintype "open_collector"))
    )
    (net (code "58") (name "Net-(U3-TMR)") (class "Default")
      (node (ref "Rtmr1") (pin "1") (pinfunction "1_1") (pintype "passive"))
      (node (ref "U3") (pin "14") (pinfunction "TMR_14") (pintype "input"))
    )
    (net (code "59") (name "Net-(U3-TS)") (class "Default")
      (node (ref "Rs1") (pin "1") (pinfunction "1_1") (pintype "passive"))
      (node (ref "U3") (pin "1") (pinfunction "TS_1") (pintype "input"))
    )
    (net (code "60") (name "unconnected-(BLE1-P04-Pad18)") (class "Default")
      (node (ref "BLE1") (pin "18") (pinfunction "P04_18") (pintype "passive"))
    )
    (net (code "61") (name "unconnected-(BLE1-P05-Pad17)") (class "Default")
      (node (ref "BLE1") (pin "17") (pinfunction "P05_17") (pintype "passive"))
    )
    (net (code "62") (name "unconnected-(BLE1-P12-Pad8)") (class "Default")
      (node (ref "BLE1") (pin "8") (pinfunction "P12_8") (pintype "passive"))
    )
    (net (code "63") (name "unconnected-(BLE1-P13-Pad9)") (class "Default")
      (node (ref "BLE1") (pin "9") (pinfunction "P13_9") (pintype "passive"))
    )
    (net (code "64") (name "unconnected-(BLE1-P14-Pad13)") (class "Default")
      (node (ref "BLE1") (pin "13") (pinfunction "P14_13") (pintype "passive"))
    )
    (net (code "65") (name "unconnected-(BLE1-P15-Pad10)") (class "Default")
      (node (ref "BLE1") (pin "10") (pinfunction "P15_10") (pintype "passive"))
    )
    (net (code "66") (name "unconnected-(BLE1-P16-Pad6)") (class "Default")
      (node (ref "BLE1") (pin "6") (pinfunction "P16_6") (pintype "passive"))
    )
    (net (code "67") (name "unconnected-(BLE1-P17-Pad5)") (class "Default")
      (node (ref "BLE1") (pin "5") (pinfunction "P17_5") (pintype "passive"))
    )
    (net (code "68") (name "unconnected-(BLE1-P20-Pad4)") (class "Default")
      (node (ref "BLE1") (pin "4") (pinfunction "P20_4") (pintype "passive"))
    )
    (net (code "69") (name "unconnected-(BLE1-P21-Pad3)") (class "Default")
      (node (ref "BLE1") (pin "3") (pinfunction "P21_3") (pintype "passive"))
    )
    (net (code "70") (name "unconnected-(BLE1-P22-Pad2)") (class "Default")
      (node (ref "BLE1") (pin "2") (pinfunction "P22_2") (pintype "passive"))
    )
    (net (code "71") (name "unconnected-(BLE1-RST-Pad23)") (class "Default")
      (node (ref "BLE1") (pin "23") (pinfunction "RST_23") (pintype "passive"))
    )
    (net (code "72") (name "unconnected-(BLE1-SCK-Pad11)") (class "Default")
      (node (ref "BLE1") (pin "11") (pinfunction "SCK_11") (pintype "passive"))
    )
    (net (code "73") (name "unconnected-(BLE1-SDA-Pad12)") (class "Default")
      (node (ref "BLE1") (pin "12") (pinfunction "SDA_12") (pintype "passive"))
    )
    (net (code "74") (name "unconnected-(REG1-OUTPUT-Pad4)") (class "Default")
      (node (ref "REG1") (pin "4") (pinfunction "OUTPUT_4") (pintype "output"))
    )
    (net (code "75") (name "unconnected-(REG2-OUTPUT-Pad4)") (class "Default")
      (node (ref "REG2") (pin "4") (pinfunction "OUTPUT_4") (pintype "output"))
    )
    (net (code "76") (name "unconnected-(U2B-DNC-Pad6)") (class "Default")
      (node (ref "U2") (pin "6") (pinfunction "DNC_6") (pintype "passive"))
    )
    (net (code "77") (name "unconnected-(U2B-DNC-Pad7)") (class "Default")
      (node (ref "U2") (pin "7") (pinfunction "DNC_7") (pintype "passive"))
    )
    (net (code "78") (name "unconnected-(U2B-DNC-Pad10)") (class "Default")
      (node (ref "U2") (pin "10") (pinfunction "DNC_10") (pintype "passive"))
    )
    (net (code "79") (name "unconnected-(U2B-DNC-Pad17)") (class "Default")
      (node (ref "U2") (pin "17") (pinfunction "DNC_17") (pintype "passive"))
    )
    (net (code "80") (name "unconnected-(U2B-DNC-Pad18)") (class "Default")
      (node (ref "U2") (pin "18") (pinfunction "DNC_18") (pintype "passive"))
    )
    (net (code "81") (name "unconnected-(U2B-DNC-Pad19)") (class "Default")
      (node (ref "U2") (pin "19") (pinfunction "DNC_19") (pintype "passive"))
    )
  )
)
